# Boardv.net
KiCad netlist of a schematic drawn in EAGLE
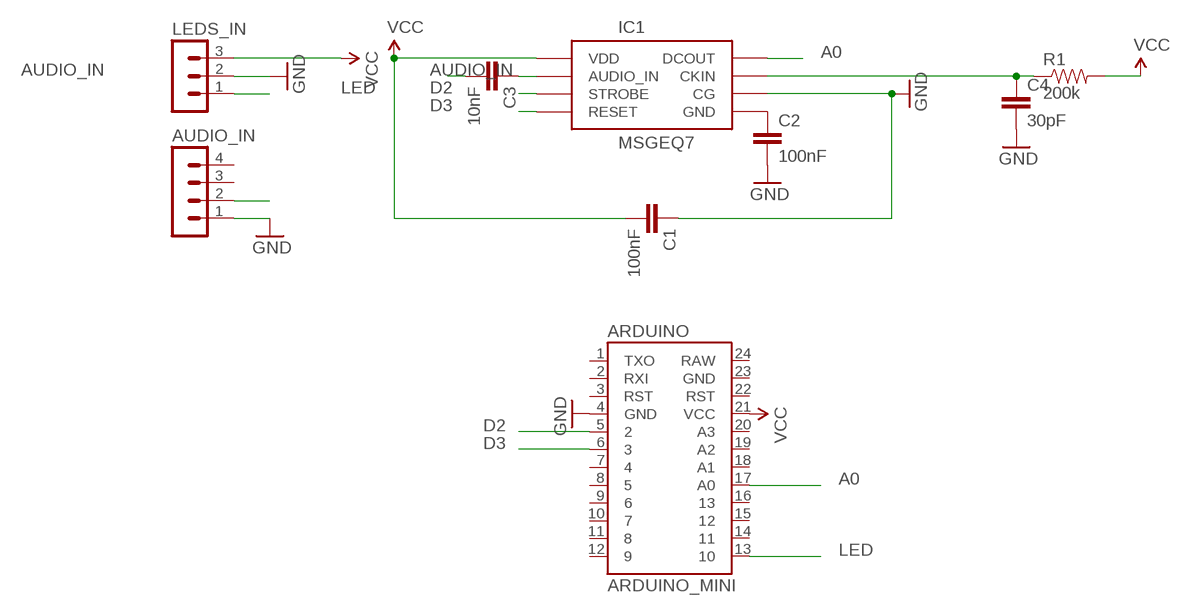
[diagram p0: schematic, sheet 1]

(export (version "E")
  (design (tool "Eeschema 10.0.6"))
  (components
    (comp (ref "ARDUINO")
      (value "ARDUINO_MINI")
      (footprint "eagle-import:ARDUINO_MINI")
      (libsource (lib "eagle-import") (part "ARDUINO_MINI"))
    )
    (comp (ref "AUDIO_IN")
      (value "MA04-1")
      (footprint "eagle-import:MA04-1")
      (libsource (lib "eagle-import") (part "MA04-1"))
    )
    (comp (ref "C1")
      (value "100nF")
      (footprint "eagle-import:CAP-PTH-SMALL-KIT")
      (libsource (lib "eagle-import") (part "0.1UF-50V-20%(PTH)KIT-EZ"))
    )
    (comp (ref "C2")
      (value "100nF")
      (footprint "eagle-import:CAP-PTH-SMALL-KIT")
      (libsource (lib "eagle-import") (part "0.1UF-50V-20%(PTH)KIT-EZ"))
    )
    (comp (ref "C3")
      (value "10nF")
      (footprint "eagle-import:CAP-PTH-SMALL-KIT")
      (libsource (lib "eagle-import") (part "0.1UF-50V-20%(PTH)KIT-EZ"))
    )
    (comp (ref "C4")
      (value "30pF")
      (footprint "eagle-import:CAP-PTH-SMALL-KIT")
      (libsource (lib "eagle-import") (part "0.1UF-50V-20%(PTH)KIT-EZ"))
    )
    (comp (ref "IC1")
      (value "MSGEQ7DIL")
      (footprint "eagle-import:DIL-08")
      (libsource (lib "eagle-import") (part "MSGEQ7DIL"))
    )
    (comp (ref "LEDS_IN")
      (value "MA03-1")
      (footprint "eagle-import:MA03-1")
      (libsource (lib "eagle-import") (part "MA03-1"))
    )
    (comp (ref "R1")
      (value "200k")
      (footprint "eagle-import:AXIAL-0.3-KIT")
      (libsource (lib "eagle-import") (part "10KOHM1/6W5%(PTH)KIT"))
    )
  )
  (nets
    (net (code "1") (name "/A0") (class "Default")
      (node (ref "ARDUINO") (pin "17") (pinfunction "A0_17") (pintype "bidirectional"))
      (node (ref "IC1") (pin "3") (pinfunction "DCOUT_3") (pintype "bidirectional"))
    )
    (net (code "2") (name "/AUDIO_IN") (class "Default")
      (node (ref "AUDIO_IN") (pin "2") (pinfunction "2_2") (pintype "passive"))
      (node (ref "C3") (pin "2") (pinfunction "2_2") (pintype "passive"))
    )
    (net (code "3") (name "/D2") (class "Default")
      (node (ref "ARDUINO") (pin "5") (pinfunction "2_5") (pintype "bidirectional"))
      (node (ref "IC1") (pin "4") (pinfunction "STROBE_4") (pintype "input"))
    )
    (net (code "4") (name "/D3") (class "Default")
      (node (ref "ARDUINO") (pin "6") (pinfunction "3_6") (pintype "bidirectional"))
      (node (ref "IC1") (pin "7") (pinfunction "RESET_7") (pintype "input"))
    )
    (net (code "5") (name "/LED") (class "Default")
      (node (ref "ARDUINO") (pin "13") (pinfunction "10_13") (pintype "bidirectional"))
      (node (ref "LEDS_IN") (pin "1") (pinfunction "1_1") (pintype "passive"))
    )
    (net (code "6") (name "GND") (class "Default")
      (node (ref "ARDUINO") (pin "4") (pinfunction "GND_4") (pintype "bidirectional"))
      (node (ref "AUDIO_IN") (pin "1") (pinfunction "1_1") (pintype "passive"))
      (node (ref "C1") (pin "1") (pinfunction "1_1") (pintype "passive"))
      (node (ref "C2") (pin "2") (pinfunction "2_2") (pintype "passive"))
      (node (ref "C4") (pin "2") (pinfunction "2_2") (pintype "passive"))
      (node (ref "IC1") (pin "6") (pinfunction "CG_6") (pintype "bidirectional"))
      (node (ref "LEDS_IN") (pin "2") (pinfunction "2_2") (pintype "passive"))
    )
    (net (code "7") (name "Net-(IC1-AUDIO_IN)") (class "Default")
      (node (ref "C3") (pin "1") (pinfunction "1_1") (pintype "passive"))
      (node (ref "IC1") (pin "5") (pinfunction "AUDIO_IN_5") (pintype "input"))
    )
    (net (code "8") (name "Net-(IC1-CKIN)") (class "Default")
      (node (ref "C4") (pin "1") (pinfunction "1_1") (pintype "passive"))
      (node (ref "IC1") (pin "8") (pinfunction "CKIN_8") (pintype "bidirectional"))
      (node (ref "R1") (pin "P$1") (pinfunction "1_P$1") (pintype "passive"))
    )
    (net (code "9") (name "Net-(IC1-GND)") (class "Default")
      (node (ref "C2") (pin "1") (pinfunction "1_1") (pintype "passive"))
      (node (ref "IC1") (pin "2") (pinfunction "GND_2") (pintype "bidirectional"))
    )
    (net (code "10") (name "VCC") (class "Default")
      (node (ref "ARDUINO") (pin "21") (pinfunction "VCC_21") (pintype "bidirectional"))
      (node (ref "C1") (pin "2") (pinfunction "2_2") (pintype "passive"))
      (node (ref "IC1") (pin "1") (pinfunction "VDD_1") (pintype "input"))
      (node (ref "LEDS_IN") (pin "3") (pinfunction "3_3") (pintype "passive"))
      (node (ref "R1") (pin "P$2") (pinfunction "2_P$2") (pintype "passive"))
    )
    (net (code "11") (name "unconnected-(ARDUINO-4-Pad7)") (class "Default")
      (node (ref "ARDUINO") (pin "7") (pinfunction "4_7") (pintype "bidirectional"))
    )
    (net (code "12") (name "unconnected-(ARDUINO-5-Pad8)") (class "Default")
      (node (ref "ARDUINO") (pin "8") (pinfunction "5_8") (pintype "bidirectional"))
    )
    (net (code "13") (name "unconnected-(ARDUINO-6-Pad9)") (class "Default")
      (node (ref "ARDUINO") (pin "9") (pinfunction "6_9") (pintype "bidirectional"))
    )
    (net (code "14") (name "unconnected-(ARDUINO-7-Pad10)") (class "Default")
      (node (ref "ARDUINO") (pin "10") (pinfunction "7_10") (pintype "bidirectional"))
    )
    (net (code "15") (name "unconnected-(ARDUINO-8-Pad11)") (class "Default")
      (node (ref "ARDUINO") (pin "11") (pinfunction "8_11") (pintype "bidirectional"))
    )
    (net (code "16") (name "unconnected-(ARDUINO-9-Pad12)") (class "Default")
      (node (ref "ARDUINO") (pin "12") (pinfunction "9_12") (pintype "bidirectional"))
    )
    (net (code "17") (name "unconnected-(ARDUINO-11-Pad14)") (class "Default")
      (node (ref "ARDUINO") (pin "14") (pinfunction "11_14") (pintype "bidirectional"))
    )
    (net (code "18") (name "unconnected-(ARDUINO-12-Pad15)") (class "Default")
      (node (ref "ARDUINO") (pin "15") (pinfunction "12_15") (pintype "bidirectional"))
    )
    (net (code "19") (name "unconnected-(ARDUINO-13-Pad16)") (class "Default")
      (node (ref "ARDUINO") (pin "16") (pinfunction "13_16") (pintype "bidirectional"))
    )
    (net (code "20") (name "unconnected-(ARDUINO-A1-Pad18)") (class "Default")
      (node (ref "ARDUINO") (pin "18") (pinfunction "A1_18") (pintype "bidirectional"))
    )
    (net (code "21") (name "unconnected-(ARDUINO-A2-Pad19)") (class "Default")
      (node (ref "ARDUINO") (pin "19") (pinfunction "A2_19") (pintype "bidirectional"))
    )
    (net (code "22") (name "unconnected-(ARDUINO-A3-Pad20)") (class "Default")
      (node (ref "ARDUINO") (pin "20") (pinfunction "A3_20") (pintype "bidirectional"))
    )
    (net (code "23") (name "unconnected-(ARDUINO-GND-Pad23)") (class "Default")
      (node (ref "ARDUINO") (pin "23") (pinfunction "GND_23") (pintype "bidirectional"))
    )
    (net (code "24") (name "unconnected-(ARDUINO-RAW-Pad24)") (class "Default")
      (node (ref "ARDUINO") (pin "24") (pinfunction "RAW_24") (pintype "bidirectional"))
    )
    (net (code "25") (name "unconnected-(ARDUINO-RST-Pad3)") (class "Default")
      (node (ref "ARDUINO") (pin "3") (pinfunction "RST_3") (pintype "bidirectional"))
    )
    (net (code "26") (name "unconnected-(ARDUINO-RST-Pad22)") (class "Default")
      (node (ref "ARDUINO") (pin "22") (pinfunction "RST_22") (pintype "bidirectional"))
    )
    (net (code "27") (name "unconnected-(ARDUINO-RXI-Pad2)") (class "Default")
      (node (ref "ARDUINO") (pin "2") (pinfunction "RXI_2") (pintype "bidirectional"))
    )
    (net (code "28") (name "unconnected-(ARDUINO-TXO-Pad1)") (class "Default")
      (node (ref "ARDUINO") (pin "1") (pinfunction "TXO_1") (pintype "bidirectional"))
    )
    (net (code "29") (name "unconnected-(AUDIO_IN-Pad3)") (class "Default")
      (node (ref "AUDIO_IN") (pin "3") (pinfunction "3_3") (pintype "passive"))
    )
    (net (code "30") (name "unconnected-(AUDIO_IN-Pad4)") (class "Default")
      (node (ref "AUDIO_IN") (pin "4") (pinfunction "4_4") (pintype "passive"))
    )
  )
)
